# pickup.net
KiCad netlist of a schematic drawn in EasyEDA
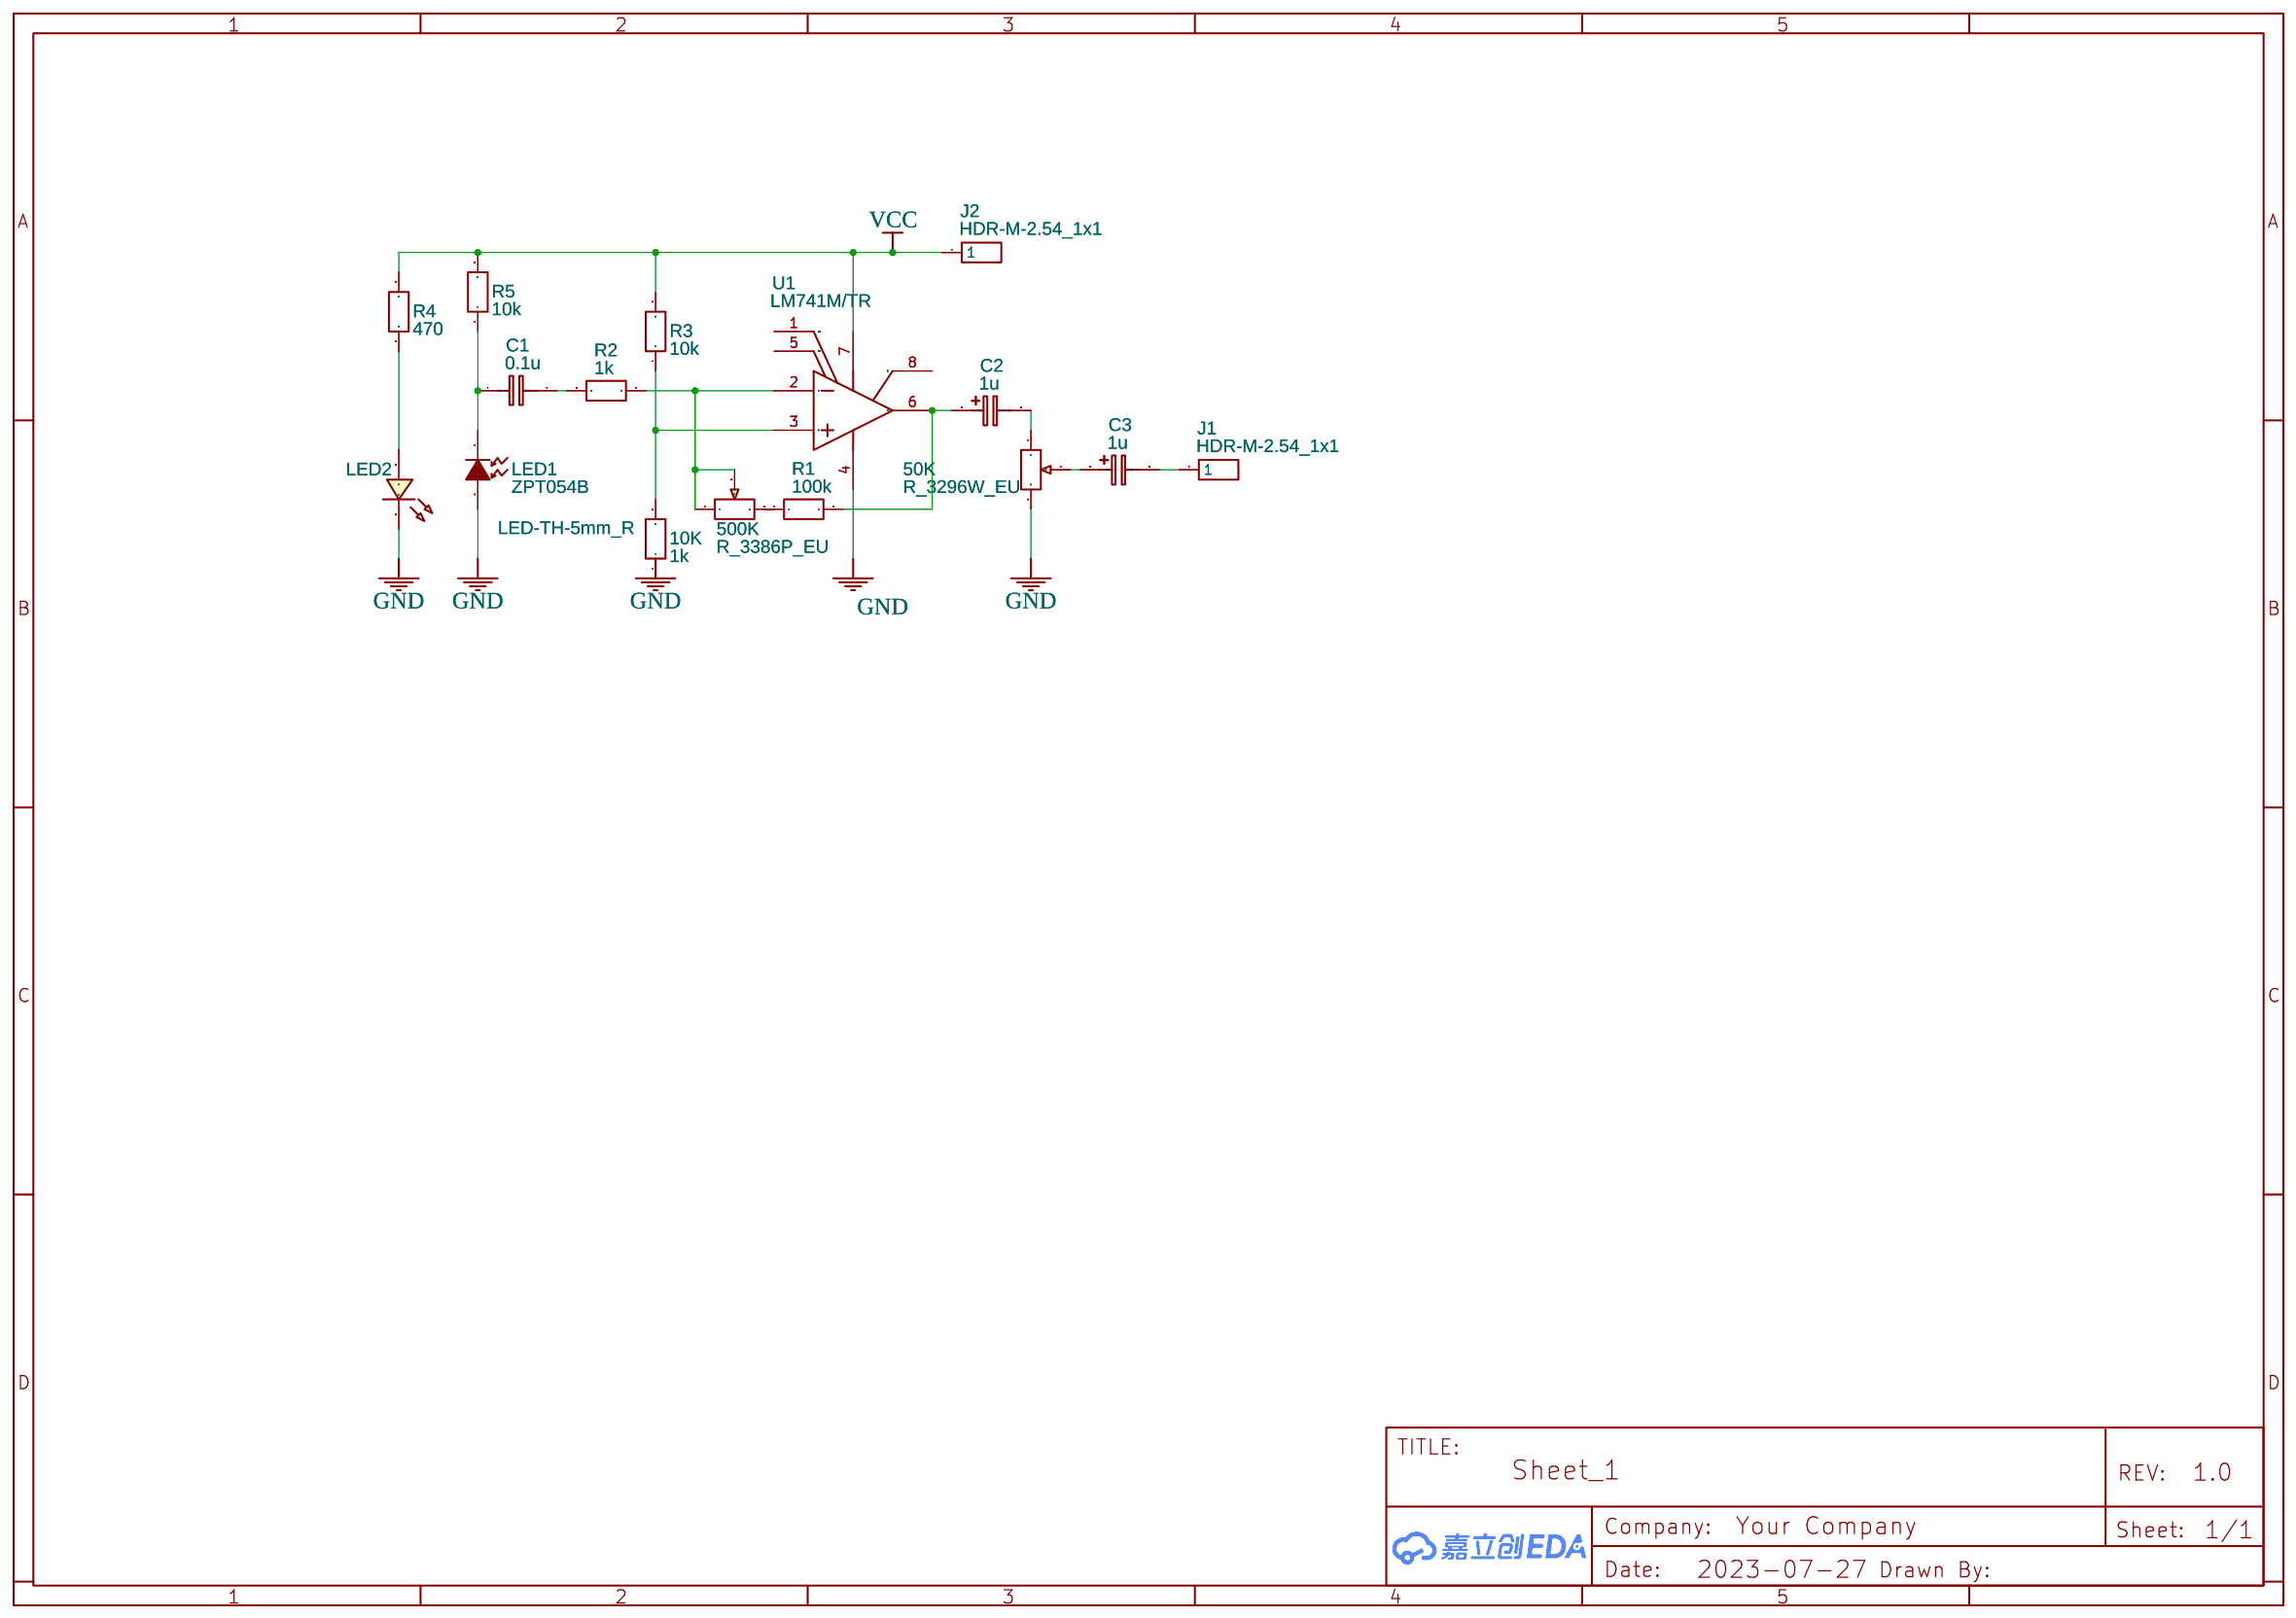
[diagram p0: schematic sheet]

(export (version "E")
  (design (tool "Eeschema 10.0.6"))
  (components
    (comp (ref "10K") (value "1k") (libsource (lib "") (part "R_0603_EU_2")))
    (comp (ref "50K") (value "R_3296W_EU") (libsource (lib "") (part "R_3296W_EU")))
    (comp (ref "500K") (value "R_3386P_EU") (libsource (lib "") (part "R_3386P_EU")))
    (comp (ref "C1") (value "0.1u") (libsource (lib "") (part "C_0603_EU")))
    (comp (ref "C2") (value "1u") (libsource (lib "") (part "C_Tan_SMD_A_EU")))
    (comp (ref "C3") (value "1u") (libsource (lib "") (part "C_Tan_SMD_A_EU_1")))
    (comp (ref "J1")
      (value "HDR-M-2.54_1x1")
      (fields (field (name "BOM_Supplier Part") "C81276"))
      (libsource (lib "") (part "HDR-M-2.54_1x1"))
    )
    (comp (ref "J2")
      (value "HDR-M-2.54_1x1")
      (fields (field (name "BOM_Supplier Part") "C81276"))
      (libsource (lib "") (part "HDR-M-2.54_1x1"))
    )
    (comp (ref "LED1")
      (value "ZPT054B")
      (fields (field (name "Manufacturer") "Chau Light"))
      (libsource (lib "") (part "ZPT054B"))
    )
    (comp (ref "LED2")
      (value "LED-TH-5mm_R")
      (fields
        (field (name "BOM_Manufacturer Part") "333-2SURD/S530-A3")
        (field (name "BOM_Supplier Part") "C87271")
      )
      (libsource (lib "") (part "LED-TH-5mm_R"))
    )
    (comp (ref "R1") (value "100k") (libsource (lib "") (part "R_0603_EU")))
    (comp (ref "R2") (value "1k") (libsource (lib "") (part "R_0603_EU")))
    (comp (ref "R3") (value "10k") (libsource (lib "") (part "R_0603_EU_1")))
    (comp (ref "R4") (value "470") (libsource (lib "") (part "R_0603_EU_1")))
    (comp (ref "R5") (value "10k") (libsource (lib "") (part "R_0603_EU_1")))
    (comp (ref "U1")
      (value "LM741M/TR")
      (fields (field (name "Manufacturer") "HGSEMI(华冠)"))
      (libsource (lib "") (part "LM741M/TR"))
    )
  )
  (nets
    (net (code "1") (name "GND") (class "Default")
      (node (ref "10K") (pin "1") (pinfunction "1_1") (pintype "unspecified"))
      (node (ref "50K") (pin "3") (pinfunction "3_3") (pintype "input"))
      (node (ref "LED1") (pin "2") (pinfunction "C_2") (pintype "input"))
      (node (ref "LED2") (pin "2") (pinfunction "2_2") (pintype "unspecified"))
      (node (ref "U1") (pin "4") (pinfunction "V-_4") (pintype "passive"))
    )
    (net (code "2") (name "Net-(50K-Pad1)") (class "Default")
      (node (ref "50K") (pin "1") (pinfunction "1_1") (pintype "input"))
      (node (ref "C2") (pin "2") (pinfunction "2_2") (pintype "unspecified"))
    )
    (net (code "3") (name "Net-(50K-Pad2)") (class "Default")
      (node (ref "50K") (pin "2") (pinfunction "2_2") (pintype "input"))
      (node (ref "C3") (pin "1") (pinfunction "1_1") (pintype "unspecified"))
    )
    (net (code "4") (name "Net-(500K-Pad3)") (class "Default")
      (node (ref "500K") (pin "3") (pinfunction "3_3") (pintype "input"))
      (node (ref "R1") (pin "1") (pinfunction "1_1") (pintype "unspecified"))
    )
    (net (code "5") (name "Net-(C1-Pad2)") (class "Default")
      (node (ref "C1") (pin "2") (pinfunction "2_2") (pintype "unspecified"))
      (node (ref "R2") (pin "1") (pinfunction "1_1") (pintype "unspecified"))
    )
    (net (code "6") (name "Net-(C3-Pad2)") (class "Default")
      (node (ref "C3") (pin "2") (pinfunction "2_2") (pintype "unspecified"))
      (node (ref "J1") (pin "1") (pinfunction "1_1") (pintype "input"))
    )
    (net (code "7") (name "Net-(LED1-E)") (class "Default")
      (node (ref "C1") (pin "1") (pinfunction "1_1") (pintype "unspecified"))
      (node (ref "LED1") (pin "1") (pinfunction "E_1") (pintype "input"))
      (node (ref "R5") (pin "1") (pinfunction "1_1") (pintype "unspecified"))
    )
    (net (code "8") (name "Net-(LED2-Pad1)") (class "Default")
      (node (ref "LED2") (pin "1") (pinfunction "1_1") (pintype "unspecified"))
      (node (ref "R4") (pin "1") (pinfunction "1_1") (pintype "unspecified"))
    )
    (net (code "9") (name "Net-(U1-IN+)") (class "Default")
      (node (ref "10K") (pin "2") (pinfunction "2_2") (pintype "unspecified"))
      (node (ref "R3") (pin "1") (pinfunction "1_1") (pintype "unspecified"))
      (node (ref "U1") (pin "3") (pinfunction "IN+_3") (pintype "unspecified"))
    )
    (net (code "10") (name "Net-(U1-IN-)") (class "Default")
      (node (ref "500K") (pin "1") (pinfunction "1_1") (pintype "input"))
      (node (ref "500K") (pin "2") (pinfunction "2_2") (pintype "input"))
      (node (ref "R2") (pin "2") (pinfunction "2_2") (pintype "unspecified"))
      (node (ref "U1") (pin "2") (pinfunction "IN-_2") (pintype "unspecified"))
    )
    (net (code "11") (name "Net-(U1-OUT)") (class "Default")
      (node (ref "C2") (pin "1") (pinfunction "1_1") (pintype "unspecified"))
      (node (ref "R1") (pin "2") (pinfunction "2_2") (pintype "unspecified"))
      (node (ref "U1") (pin "6") (pinfunction "OUT_6") (pintype "output"))
    )
    (net (code "12") (name "VCC") (class "Default")
      (node (ref "J2") (pin "1") (pinfunction "1_1") (pintype "input"))
      (node (ref "R3") (pin "2") (pinfunction "2_2") (pintype "unspecified"))
      (node (ref "R4") (pin "2") (pinfunction "2_2") (pintype "unspecified"))
      (node (ref "R5") (pin "2") (pinfunction "2_2") (pintype "unspecified"))
      (node (ref "U1") (pin "7") (pinfunction "V+_7") (pintype "passive"))
    )
    (net (code "13") (name "unconnected-(U1-NC-Pad8)") (class "Default")
      (node (ref "U1") (pin "8") (pinfunction "NC_8") (pintype "unspecified"))
    )
    (net (code "14") (name "unconnected-(U1-OFFSET_NULL-Pad1)") (class "Default")
      (node (ref "U1") (pin "1") (pinfunction "OFFSET_NULL_1") (pintype "unspecified"))
    )
    (net (code "15") (name "unconnected-(U1-OFFSET_NULL-Pad5)") (class "Default")
      (node (ref "U1") (pin "5") (pinfunction "OFFSET_NULL_5") (pintype "unspecified"))
    )
  )
)
